# ROOM_MICRO.net
KiCad netlist of a schematic drawn in Altium Designer
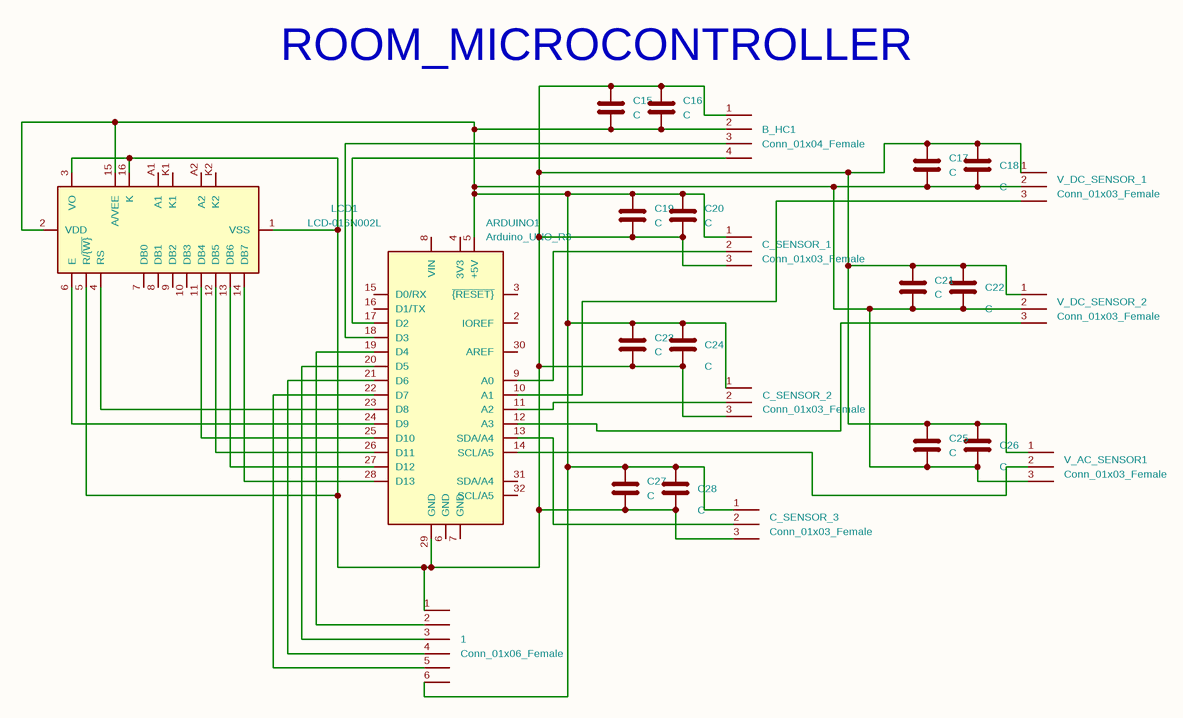
[diagram p0: ROOM_MICRO.SchDoc]

(export (version "E")
  (design (tool "Eeschema 10.0.6"))
  (components
    (comp (ref "1")
      (value "Conn_01x06_Female")
      (footprint "PinHeader_1x06_P2.54mm_Vertical")
      (libsource (lib "Connector") (part "Conn_01x06_Female"))
    )
    (comp (ref "ARDUINO1")
      (value "Arduino_UNO_R3")
      (footprint "Arduino_UNO_R3")
      (libsource (lib "MCU_Module") (part "Arduino_UNO_R3"))
    )
    (comp (ref "B_HC1")
      (value "Conn_01x04_Female")
      (footprint "PinHeader_1x04_P2.54mm_Vertical")
      (libsource (lib "Connector") (part "Conn_01x04_Female"))
    )
    (comp (ref "C15") (value "C") (footprint "C_0805_2012Metric") (libsource (lib "Device") (part "C")))
    (comp (ref "C16") (value "C") (footprint "C_0805_2012Metric") (libsource (lib "Device") (part "C")))
    (comp (ref "C17") (value "C") (footprint "C_0805_2012Metric") (libsource (lib "Device") (part "C")))
    (comp (ref "C18") (value "C") (footprint "C_0805_2012Metric") (libsource (lib "Device") (part "C")))
    (comp (ref "C19") (value "C") (footprint "C_0805_2012Metric") (libsource (lib "Device") (part "C")))
    (comp (ref "C20") (value "C") (footprint "C_0805_2012Metric") (libsource (lib "Device") (part "C")))
    (comp (ref "C21") (value "C") (footprint "C_0805_2012Metric") (libsource (lib "Device") (part "C")))
    (comp (ref "C22") (value "C") (footprint "C_0805_2012Metric") (libsource (lib "Device") (part "C")))
    (comp (ref "C23") (value "C") (footprint "C_0805_2012Metric") (libsource (lib "Device") (part "C")))
    (comp (ref "C24") (value "C") (footprint "C_0805_2012Metric") (libsource (lib "Device") (part "C")))
    (comp (ref "C25") (value "C") (footprint "C_0805_2012Metric") (libsource (lib "Device") (part "C")))
    (comp (ref "C26") (value "C") (footprint "C_0805_2012Metric") (libsource (lib "Device") (part "C")))
    (comp (ref "C27") (value "C") (footprint "C_0805_2012Metric") (libsource (lib "Device") (part "C")))
    (comp (ref "C28") (value "C") (footprint "C_0805_2012Metric") (libsource (lib "Device") (part "C")))
    (comp (ref "C_SENSOR_1")
      (value "Conn_01x03_Female")
      (footprint "PinHeader_1x03_P2.54mm_Vertical")
      (libsource (lib "Connector") (part "Conn_01x03_Female"))
    )
    (comp (ref "C_SENSOR_2")
      (value "Conn_01x03_Female")
      (footprint "PinHeader_1x03_P2.54mm_Vertical")
      (libsource (lib "Connector") (part "Conn_01x03_Female"))
    )
    (comp (ref "C_SENSOR_3")
      (value "Conn_01x03_Female")
      (footprint "PinHeader_1x03_P2.54mm_Vertical")
      (libsource (lib "Connector") (part "Conn_01x03_Female"))
    )
    (comp (ref "LCD1")
      (value "LCD-016N002L")
      (footprint "LCD-016N002L")
      (libsource (lib "Display_Character") (part "LCD-016N002L"))
    )
    (comp (ref "V_AC_SENSOR1")
      (value "Conn_01x03_Female")
      (footprint "PinHeader_1x03_P2.54mm_Vertical")
      (libsource (lib "Connector") (part "Conn_01x03_Female"))
    )
    (comp (ref "V_DC_SENSOR_1")
      (value "Conn_01x03_Female")
      (footprint "PinHeader_1x03_P2.54mm_Vertical")
      (libsource (lib "Connector") (part "Conn_01x03_Female"))
    )
    (comp (ref "V_DC_SENSOR_2")
      (value "Conn_01x03_Female")
      (footprint "PinHeader_1x03_P2.54mm_Vertical")
      (libsource (lib "Connector") (part "Conn_01x03_Female"))
    )
  )
  (nets
    (net (code "1") (name "Net-(1-Pin_1)") (class "Default")
      (node (ref "1") (pin "1") (pinfunction "Pin_1_1") (pintype "passive"))
      (node (ref "ARDUINO1") (pin "29") (pinfunction "GND_29") (pintype "passive"))
      (node (ref "B_HC1") (pin "1") (pinfunction "Pin_1_1") (pintype "passive"))
      (node (ref "C15") (pin "1") (pinfunction "1_1") (pintype "passive"))
      (node (ref "C16") (pin "1") (pinfunction "1_1") (pintype "passive"))
      (node (ref "C17") (pin "1") (pinfunction "1_1") (pintype "passive"))
      (node (ref "C18") (pin "1") (pinfunction "1_1") (pintype "passive"))
      (node (ref "C19") (pin "2") (pinfunction "2_2") (pintype "passive"))
      (node (ref "C20") (pin "2") (pinfunction "2_2") (pintype "passive"))
      (node (ref "C21") (pin "1") (pinfunction "1_1") (pintype "passive"))
      (node (ref "C22") (pin "1") (pinfunction "1_1") (pintype "passive"))
      (node (ref "C23") (pin "2") (pinfunction "2_2") (pintype "passive"))
      (node (ref "C24") (pin "2") (pinfunction "2_2") (pintype "passive"))
      (node (ref "C25") (pin "1") (pinfunction "1_1") (pintype "passive"))
      (node (ref "C26") (pin "1") (pinfunction "1_1") (pintype "passive"))
      (node (ref "C27") (pin "2") (pinfunction "2_2") (pintype "passive"))
      (node (ref "C28") (pin "2") (pinfunction "2_2") (pintype "passive"))
      (node (ref "C_SENSOR_1") (pin "3") (pinfunction "Pin_3_3") (pintype "passive"))
      (node (ref "C_SENSOR_2") (pin "3") (pinfunction "Pin_3_3") (pintype "passive"))
      (node (ref "C_SENSOR_3") (pin "3") (pinfunction "Pin_3_3") (pintype "passive"))
      (node (ref "LCD1") (pin "1") (pinfunction "VSS_1") (pintype "passive"))
      (node (ref "LCD1") (pin "16") (pinfunction "K_16") (pintype "passive"))
      (node (ref "LCD1") (pin "3") (pinfunction "VO_3") (pintype "passive"))
      (node (ref "LCD1") (pin "5") (pinfunction "R/~{{W}}_5") (pintype "passive"))
      (node (ref "V_AC_SENSOR1") (pin "1") (pinfunction "Pin_1_1") (pintype "passive"))
      (node (ref "V_DC_SENSOR_1") (pin "1") (pinfunction "Pin_1_1") (pintype "passive"))
      (node (ref "V_DC_SENSOR_2") (pin "1") (pinfunction "Pin_1_1") (pintype "passive"))
    )
    (net (code "2") (name "Net-(1-Pin_2)") (class "Default")
      (node (ref "1") (pin "2") (pinfunction "Pin_2_2") (pintype "passive"))
      (node (ref "ARDUINO1") (pin "19") (pinfunction "D4_19") (pintype "passive"))
    )
    (net (code "3") (name "Net-(1-Pin_3)") (class "Default")
      (node (ref "1") (pin "3") (pinfunction "Pin_3_3") (pintype "passive"))
      (node (ref "ARDUINO1") (pin "20") (pinfunction "D5_20") (pintype "passive"))
    )
    (net (code "4") (name "Net-(1-Pin_4)") (class "Default")
      (node (ref "1") (pin "4") (pinfunction "Pin_4_4") (pintype "passive"))
      (node (ref "ARDUINO1") (pin "21") (pinfunction "D6_21") (pintype "passive"))
    )
    (net (code "5") (name "Net-(1-Pin_5)") (class "Default")
      (node (ref "1") (pin "5") (pinfunction "Pin_5_5") (pintype "passive"))
      (node (ref "ARDUINO1") (pin "22") (pinfunction "D7_22") (pintype "passive"))
    )
    (net (code "6") (name "Net-(1-Pin_6)") (class "Default")
      (node (ref "1") (pin "6") (pinfunction "Pin_6_6") (pintype "passive"))
      (node (ref "ARDUINO1") (pin "5") (pinfunction "+5V_5") (pintype "passive"))
      (node (ref "B_HC1") (pin "2") (pinfunction "Pin_2_2") (pintype "passive"))
      (node (ref "C15") (pin "2") (pinfunction "2_2") (pintype "passive"))
      (node (ref "C16") (pin "2") (pinfunction "2_2") (pintype "passive"))
      (node (ref "C17") (pin "2") (pinfunction "2_2") (pintype "passive"))
      (node (ref "C18") (pin "2") (pinfunction "2_2") (pintype "passive"))
      (node (ref "C19") (pin "1") (pinfunction "1_1") (pintype "passive"))
      (node (ref "C20") (pin "1") (pinfunction "1_1") (pintype "passive"))
      (node (ref "C21") (pin "2") (pinfunction "2_2") (pintype "passive"))
      (node (ref "C22") (pin "2") (pinfunction "2_2") (pintype "passive"))
      (node (ref "C23") (pin "1") (pinfunction "1_1") (pintype "passive"))
      (node (ref "C24") (pin "1") (pinfunction "1_1") (pintype "passive"))
      (node (ref "C25") (pin "2") (pinfunction "2_2") (pintype "passive"))
      (node (ref "C26") (pin "2") (pinfunction "2_2") (pintype "passive"))
      (node (ref "C27") (pin "1") (pinfunction "1_1") (pintype "passive"))
      (node (ref "C28") (pin "1") (pinfunction "1_1") (pintype "passive"))
      (node (ref "C_SENSOR_1") (pin "1") (pinfunction "Pin_1_1") (pintype "passive"))
      (node (ref "C_SENSOR_2") (pin "1") (pinfunction "Pin_1_1") (pintype "passive"))
      (node (ref "C_SENSOR_3") (pin "1") (pinfunction "Pin_1_1") (pintype "passive"))
      (node (ref "LCD1") (pin "15") (pinfunction "A/VEE_15") (pintype "passive"))
      (node (ref "LCD1") (pin "2") (pinfunction "VDD_2") (pintype "passive"))
      (node (ref "V_AC_SENSOR1") (pin "3") (pinfunction "Pin_3_3") (pintype "passive"))
      (node (ref "V_DC_SENSOR_1") (pin "2") (pinfunction "Pin_2_2") (pintype "passive"))
      (node (ref "V_DC_SENSOR_2") (pin "2") (pinfunction "Pin_2_2") (pintype "passive"))
    )
    (net (code "7") (name "Net-(ARDUINO1-A0)") (class "Default")
      (node (ref "ARDUINO1") (pin "9") (pinfunction "A0_9") (pintype "passive"))
      (node (ref "C_SENSOR_1") (pin "2") (pinfunction "Pin_2_2") (pintype "passive"))
    )
    (net (code "8") (name "Net-(ARDUINO1-A1)") (class "Default")
      (node (ref "ARDUINO1") (pin "10") (pinfunction "A1_10") (pintype "passive"))
      (node (ref "V_DC_SENSOR_1") (pin "3") (pinfunction "Pin_3_3") (pintype "passive"))
    )
    (net (code "9") (name "Net-(ARDUINO1-A2)") (class "Default")
      (node (ref "ARDUINO1") (pin "11") (pinfunction "A2_11") (pintype "passive"))
      (node (ref "C_SENSOR_2") (pin "2") (pinfunction "Pin_2_2") (pintype "passive"))
    )
    (net (code "10") (name "Net-(ARDUINO1-A3)") (class "Default")
      (node (ref "ARDUINO1") (pin "12") (pinfunction "A3_12") (pintype "passive"))
      (node (ref "V_DC_SENSOR_2") (pin "3") (pinfunction "Pin_3_3") (pintype "passive"))
    )
    (net (code "11") (name "Net-(ARDUINO1-D2)") (class "Default")
      (node (ref "ARDUINO1") (pin "17") (pinfunction "D2_17") (pintype "passive"))
      (node (ref "B_HC1") (pin "4") (pinfunction "Pin_4_4") (pintype "passive"))
    )
    (net (code "12") (name "Net-(ARDUINO1-D3)") (class "Default")
      (node (ref "ARDUINO1") (pin "18") (pinfunction "D3_18") (pintype "passive"))
      (node (ref "B_HC1") (pin "3") (pinfunction "Pin_3_3") (pintype "passive"))
    )
    (net (code "13") (name "Net-(ARDUINO1-D8)") (class "Default")
      (node (ref "ARDUINO1") (pin "23") (pinfunction "D8_23") (pintype "passive"))
      (node (ref "LCD1") (pin "4") (pinfunction "RS_4") (pintype "passive"))
    )
    (net (code "14") (name "Net-(ARDUINO1-D9)") (class "Default")
      (node (ref "ARDUINO1") (pin "24") (pinfunction "D9_24") (pintype "passive"))
      (node (ref "LCD1") (pin "6") (pinfunction "E_6") (pintype "passive"))
    )
    (net (code "15") (name "Net-(ARDUINO1-D10)") (class "Default")
      (node (ref "ARDUINO1") (pin "25") (pinfunction "D10_25") (pintype "passive"))
      (node (ref "LCD1") (pin "11") (pinfunction "DB4_11") (pintype "passive"))
    )
    (net (code "16") (name "Net-(ARDUINO1-D11)") (class "Default")
      (node (ref "ARDUINO1") (pin "26") (pinfunction "D11_26") (pintype "passive"))
      (node (ref "LCD1") (pin "12") (pinfunction "DB5_12") (pintype "passive"))
    )
    (net (code "17") (name "Net-(ARDUINO1-D12)") (class "Default")
      (node (ref "ARDUINO1") (pin "27") (pinfunction "D12_27") (pintype "passive"))
      (node (ref "LCD1") (pin "13") (pinfunction "DB6_13") (pintype "passive"))
    )
    (net (code "18") (name "Net-(ARDUINO1-D13)") (class "Default")
      (node (ref "ARDUINO1") (pin "28") (pinfunction "D13_28") (pintype "passive"))
      (node (ref "LCD1") (pin "14") (pinfunction "DB7_14") (pintype "passive"))
    )
    (net (code "19") (name "Net-(C_SENSOR_3-Pin_2)") (class "Default")
      (node (ref "ARDUINO1") (pin "13") (pinfunction "SDA/A4_13") (pintype "passive"))
      (node (ref "C_SENSOR_3") (pin "2") (pinfunction "Pin_2_2") (pintype "passive"))
    )
    (net (code "20") (name "Net-(V_AC_SENSOR1-Pin_2)") (class "Default")
      (node (ref "ARDUINO1") (pin "14") (pinfunction "SCL/A5_14") (pintype "passive"))
      (node (ref "V_AC_SENSOR1") (pin "2") (pinfunction "Pin_2_2") (pintype "passive"))
    )
    (net (code "21") (name "unconnected-(ARDUINO1-3V3-Pad4)") (class "Default")
      (node (ref "ARDUINO1") (pin "4") (pinfunction "3V3_4") (pintype "passive"))
    )
    (net (code "22") (name "unconnected-(ARDUINO1-AREF-Pad30)") (class "Default")
      (node (ref "ARDUINO1") (pin "30") (pinfunction "AREF_30") (pintype "passive"))
    )
    (net (code "23") (name "unconnected-(ARDUINO1-D0{slash}RX-Pad15)") (class "Default")
      (node (ref "ARDUINO1") (pin "15") (pinfunction "D0/RX_15") (pintype "passive"))
    )
    (net (code "24") (name "unconnected-(ARDUINO1-D1{slash}TX-Pad16)") (class "Default")
      (node (ref "ARDUINO1") (pin "16") (pinfunction "D1/TX_16") (pintype "passive"))
    )
    (net (code "25") (name "unconnected-(ARDUINO1-GND-Pad6)") (class "Default")
      (node (ref "ARDUINO1") (pin "6") (pinfunction "GND_6") (pintype "passive"))
    )
    (net (code "26") (name "unconnected-(ARDUINO1-GND-Pad7)") (class "Default")
      (node (ref "ARDUINO1") (pin "7") (pinfunction "GND_7") (pintype "passive"))
    )
    (net (code "27") (name "unconnected-(ARDUINO1-IOREF-Pad2)") (class "Default")
      (node (ref "ARDUINO1") (pin "2") (pinfunction "IOREF_2") (pintype "passive"))
    )
    (net (code "28") (name "unconnected-(ARDUINO1-NC-Pad1)") (class "Default")
      (node (ref "ARDUINO1") (pin "1") (pinfunction "NC_1") (pintype "passive"))
    )
    (net (code "29") (name "unconnected-(ARDUINO1-SCL{slash}A5-Pad32)") (class "Default")
      (node (ref "ARDUINO1") (pin "32") (pinfunction "SCL/A5_32") (pintype "passive"))
    )
    (net (code "30") (name "unconnected-(ARDUINO1-SDA{slash}A4-Pad31)") (class "Default")
      (node (ref "ARDUINO1") (pin "31") (pinfunction "SDA/A4_31") (pintype "passive"))
    )
    (net (code "31") (name "unconnected-(ARDUINO1-VIN-Pad8)") (class "Default")
      (node (ref "ARDUINO1") (pin "8") (pinfunction "VIN_8") (pintype "passive"))
    )
    (net (code "32") (name "unconnected-(ARDUINO1-~{{RESET}}-Pad3)") (class "Default")
      (node (ref "ARDUINO1") (pin "3") (pinfunction "~{{RESET}}_3") (pintype "passive"))
    )
    (net (code "33") (name "unconnected-(LCD1-DB0-Pad7)") (class "Default")
      (node (ref "LCD1") (pin "7") (pinfunction "DB0_7") (pintype "passive"))
    )
    (net (code "34") (name "unconnected-(LCD1-DB1-Pad8)") (class "Default")
      (node (ref "LCD1") (pin "8") (pinfunction "DB1_8") (pintype "passive"))
    )
    (net (code "35") (name "unconnected-(LCD1-DB2-Pad9)") (class "Default")
      (node (ref "LCD1") (pin "9") (pinfunction "DB2_9") (pintype "passive"))
    )
    (net (code "36") (name "unconnected-(LCD1-DB3-Pad10)") (class "Default")
      (node (ref "LCD1") (pin "10") (pinfunction "DB3_10") (pintype "passive"))
    )
    (net (code "37") (name "unconnected-(LCD1-PadA1)") (class "Default")
      (node (ref "LCD1") (pin "A1") (pinfunction "A1_A1") (pintype "passive"))
    )
    (net (code "38") (name "unconnected-(LCD1-PadA2)") (class "Default")
      (node (ref "LCD1") (pin "A2") (pinfunction "A2_A2") (pintype "passive"))
    )
    (net (code "39") (name "unconnected-(LCD1-PadK1)") (class "Default")
      (node (ref "LCD1") (pin "K1") (pinfunction "K1_K1") (pintype "passive"))
    )
    (net (code "40") (name "unconnected-(LCD1-PadK2)") (class "Default")
      (node (ref "LCD1") (pin "K2") (pinfunction "K2_K2") (pintype "passive"))
    )
  )
)
